# Placa_de_Cima.net
KiCad netlist of a schematic drawn in EAGLE
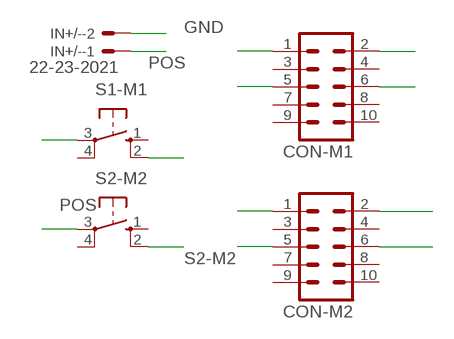
[diagram p0: schematic, sheet 1]

(export (version "E")
  (design (tool "Eeschema 10.0.6"))
  (components
    (comp (ref "CON-M1")
      (value "MA05-2")
      (footprint "eagle-import:MA05-2")
      (libsource (lib "eagle-import") (part "MA05-2"))
    )
    (comp (ref "CON-M2")
      (value "MA05-2")
      (footprint "eagle-import:MA05-2")
      (libsource (lib "eagle-import") (part "MA05-2"))
    )
    (comp (ref "IN+/-")
      (value "22-23-2021")
      (footprint "eagle-import:22-23-2021")
      (fields (field (name "MF") "MOLEX"))
      (libsource (lib "eagle-import") (part "22-23-2021"))
    )
    (comp (ref "S1-M1")
      (value "10-XX")
      (footprint "eagle-import:B3F-10XX")
      (fields (field (name "MPN") "B3F-1000"))
      (libsource (lib "eagle-import") (part "10-XX"))
    )
    (comp (ref "S2-M2")
      (value "10-XX")
      (footprint "eagle-import:B3F-10XX")
      (fields (field (name "MPN") "B3F-1000"))
      (libsource (lib "eagle-import") (part "10-XX"))
    )
  )
  (nets
    (net (code "1") (name "/GND") (class "Default")
      (node (ref "CON-M1") (pin "5") (pinfunction "5_5") (pintype "passive"))
      (node (ref "CON-M1") (pin "6") (pinfunction "6_6") (pintype "passive"))
      (node (ref "CON-M2") (pin "5") (pinfunction "5_5") (pintype "passive"))
      (node (ref "CON-M2") (pin "6") (pinfunction "6_6") (pintype "passive"))
      (node (ref "IN+/-") (pin "2") (pinfunction "S_2") (pintype "passive"))
    )
    (net (code "2") (name "/POS") (class "Default")
      (node (ref "IN+/-") (pin "1") (pinfunction "S_1") (pintype "passive"))
      (node (ref "S1-M1") (pin "3") (pinfunction "P_3") (pintype "passive"))
      (node (ref "S2-M2") (pin "3") (pinfunction "P_3") (pintype "passive"))
    )
    (net (code "3") (name "/S1-M1") (class "Default")
      (node (ref "CON-M1") (pin "1") (pinfunction "1_1") (pintype "passive"))
      (node (ref "CON-M1") (pin "2") (pinfunction "2_2") (pintype "passive"))
      (node (ref "S1-M1") (pin "2") (pinfunction "S1_2") (pintype "passive"))
    )
    (net (code "4") (name "/S2-M2") (class "Default")
      (node (ref "CON-M2") (pin "1") (pinfunction "1_1") (pintype "passive"))
      (node (ref "CON-M2") (pin "2") (pinfunction "2_2") (pintype "passive"))
      (node (ref "S2-M2") (pin "2") (pinfunction "S1_2") (pintype "passive"))
    )
    (net (code "5") (name "unconnected-(CON-M1-Pad3)") (class "Default")
      (node (ref "CON-M1") (pin "3") (pinfunction "3_3") (pintype "passive"))
    )
    (net (code "6") (name "unconnected-(CON-M1-Pad4)") (class "Default")
      (node (ref "CON-M1") (pin "4") (pinfunction "4_4") (pintype "passive"))
    )
    (net (code "7") (name "unconnected-(CON-M1-Pad7)") (class "Default")
      (node (ref "CON-M1") (pin "7") (pinfunction "7_7") (pintype "passive"))
    )
    (net (code "8") (name "unconnected-(CON-M1-Pad8)") (class "Default")
      (node (ref "CON-M1") (pin "8") (pinfunction "8_8") (pintype "passive"))
    )
    (net (code "9") (name "unconnected-(CON-M1-Pad9)") (class "Default")
      (node (ref "CON-M1") (pin "9") (pinfunction "9_9") (pintype "passive"))
    )
    (net (code "10") (name "unconnected-(CON-M1-Pad10)") (class "Default")
      (node (ref "CON-M1") (pin "10") (pinfunction "10_10") (pintype "passive"))
    )
    (net (code "11") (name "unconnected-(CON-M2-Pad3)") (class "Default")
      (node (ref "CON-M2") (pin "3") (pinfunction "3_3") (pintype "passive"))
    )
    (net (code "12") (name "unconnected-(CON-M2-Pad4)") (class "Default")
      (node (ref "CON-M2") (pin "4") (pinfunction "4_4") (pintype "passive"))
    )
    (net (code "13") (name "unconnected-(CON-M2-Pad7)") (class "Default")
      (node (ref "CON-M2") (pin "7") (pinfunction "7_7") (pintype "passive"))
    )
    (net (code "14") (name "unconnected-(CON-M2-Pad8)") (class "Default")
      (node (ref "CON-M2") (pin "8") (pinfunction "8_8") (pintype "passive"))
    )
    (net (code "15") (name "unconnected-(CON-M2-Pad9)") (class "Default")
      (node (ref "CON-M2") (pin "9") (pinfunction "9_9") (pintype "passive"))
    )
    (net (code "16") (name "unconnected-(CON-M2-Pad10)") (class "Default")
      (node (ref "CON-M2") (pin "10") (pinfunction "10_10") (pintype "passive"))
    )
    (net (code "17") (name "unconnected-(S1-M1-P1-Pad4)") (class "Default")
      (node (ref "S1-M1") (pin "4") (pinfunction "P1_4") (pintype "passive"))
    )
    (net (code "18") (name "unconnected-(S1-M1-S-Pad1)") (class "Default")
      (node (ref "S1-M1") (pin "1") (pinfunction "S_1") (pintype "passive"))
    )
    (net (code "19") (name "unconnected-(S2-M2-P1-Pad4)") (class "Default")
      (node (ref "S2-M2") (pin "4") (pinfunction "P1_4") (pintype "passive"))
    )
    (net (code "20") (name "unconnected-(S2-M2-S-Pad1)") (class "Default")
      (node (ref "S2-M2") (pin "1") (pinfunction "S_1") (pintype "passive"))
    )
  )
)
